# bot_power_supply.net
KiCad netlist of a schematic drawn in EAGLE
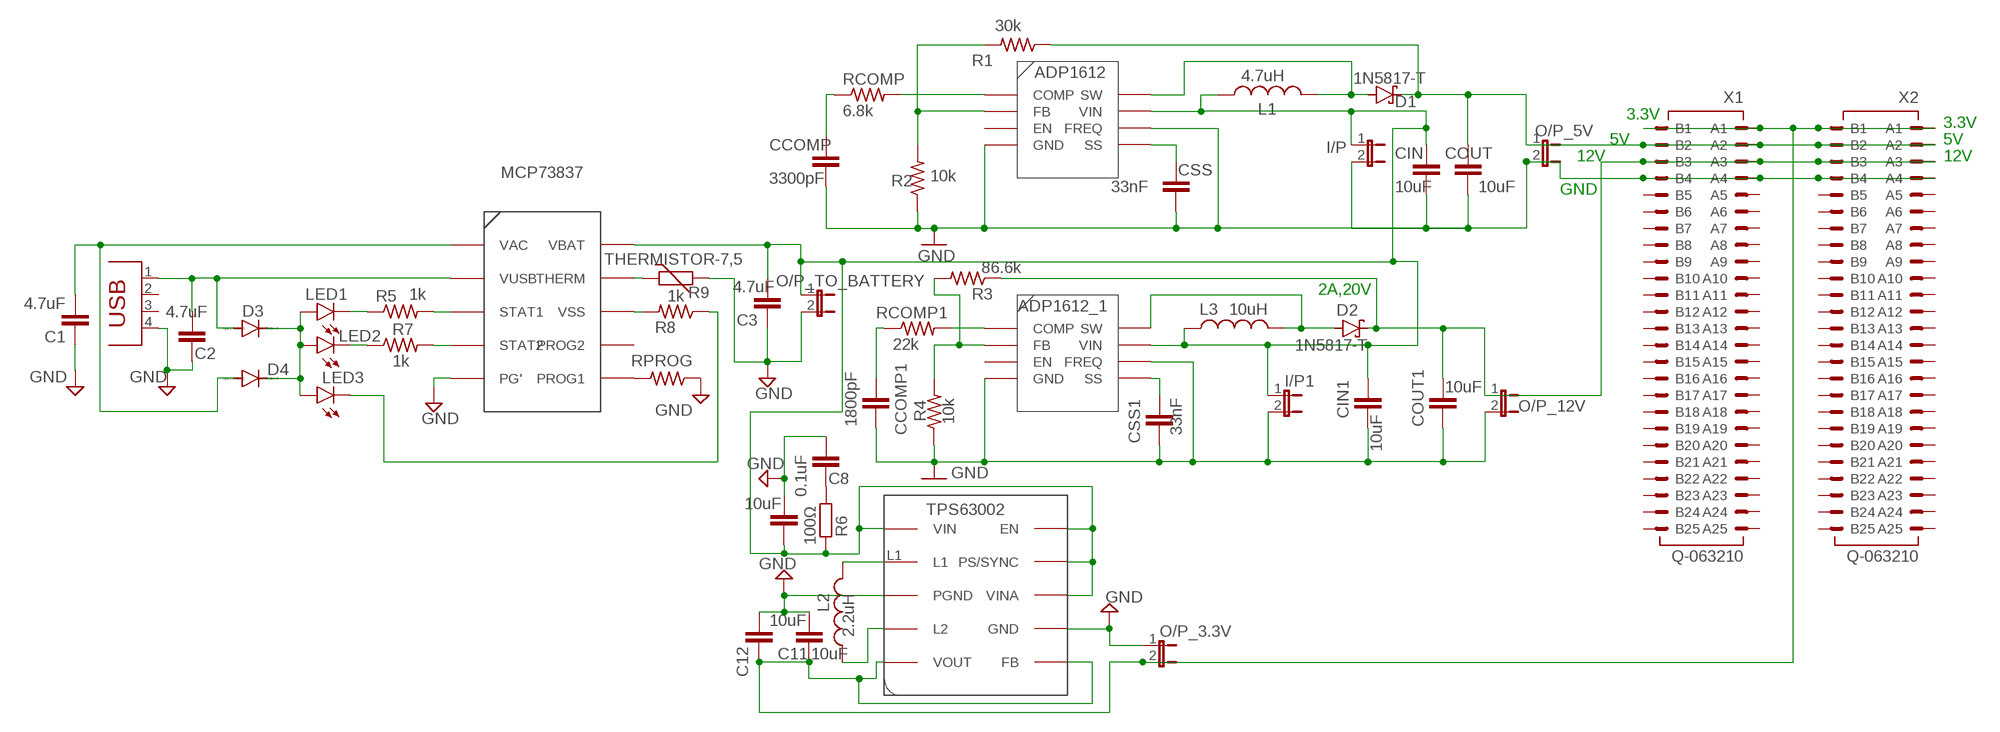
[diagram p0: schematic, sheet 1]

(export (version "E")
  (design (tool "Eeschema 10.0.6"))
  (components
    (comp (ref "ADP1612")
      (value "ADP1612_DEV")
      (footprint "eagle-import:ADP1612_FOOT")
      (libsource (lib "eagle-import") (part "ADP1612_DEV"))
    )
    (comp (ref "ADP1612_1")
      (value "ADP1612_DEV")
      (footprint "eagle-import:ADP1612_FOOT")
      (libsource (lib "eagle-import") (part "ADP1612_DEV"))
    )
    (comp (ref "C1")
      (value "4.7uF")
      (footprint "eagle-import:C2.5-3")
      (libsource (lib "eagle-import") (part "C2,5-3"))
    )
    (comp (ref "C2")
      (value "4.7uF")
      (footprint "eagle-import:C2.5-3")
      (libsource (lib "eagle-import") (part "C2,5-3"))
    )
    (comp (ref "C3")
      (value "4.7uF")
      (footprint "eagle-import:C2.5-3")
      (libsource (lib "eagle-import") (part "C2,5-3"))
    )
    (comp (ref "C8")
      (value "0.1uF")
      (footprint "eagle-import:C2.5-2")
      (libsource (lib "eagle-import") (part "C2.5/2"))
    )
    (comp (ref "C10")
      (value "10uF")
      (footprint "eagle-import:C2.5-2")
      (libsource (lib "eagle-import") (part "C2.5/2"))
    )
    (comp (ref "C11")
      (value "10uF")
      (footprint "eagle-import:C2.5-2")
      (libsource (lib "eagle-import") (part "C2.5/2"))
    )
    (comp (ref "C12")
      (value "10uF")
      (footprint "eagle-import:C2.5-2")
      (libsource (lib "eagle-import") (part "C2.5/2"))
    )
    (comp (ref "CCOMP")
      (value "3300pF")
      (footprint "eagle-import:C2.5-3")
      (libsource (lib "eagle-import") (part "C2,5-3"))
    )
    (comp (ref "CCOMP1")
      (value "1800pF")
      (footprint "eagle-import:C2.5-3")
      (libsource (lib "eagle-import") (part "C2,5-3"))
    )
    (comp (ref "CIN")
      (value "10uF")
      (footprint "eagle-import:C2.5-3")
      (libsource (lib "eagle-import") (part "C2,5-3"))
    )
    (comp (ref "CIN1")
      (value "10uF")
      (footprint "eagle-import:C2.5-3")
      (libsource (lib "eagle-import") (part "C2,5-3"))
    )
    (comp (ref "COUT")
      (value "10uF")
      (footprint "eagle-import:C2.5-3")
      (libsource (lib "eagle-import") (part "C2,5-3"))
    )
    (comp (ref "COUT1")
      (value "10uF")
      (footprint "eagle-import:C2.5-3")
      (libsource (lib "eagle-import") (part "C2,5-3"))
    )
    (comp (ref "CSS")
      (value "33nF")
      (footprint "eagle-import:C2.5-3")
      (libsource (lib "eagle-import") (part "C2,5-3"))
    )
    (comp (ref "CSS1")
      (value "33nF")
      (footprint "eagle-import:C2.5-3")
      (libsource (lib "eagle-import") (part "C2,5-3"))
    )
    (comp (ref "D1")
      (value "1N5817-T")
      (footprint "eagle-import:DO41-7.6")
      (libsource (lib "eagle-import") (part "1N5817-T"))
    )
    (comp (ref "D2")
      (value "1N5817-T")
      (footprint "eagle-import:DO41-7.6")
      (libsource (lib "eagle-import") (part "1N5817-T"))
    )
    (comp (ref "D3")
      (value "1N4004")
      (footprint "eagle-import:DO41-10")
      (libsource (lib "eagle-import") (part "1N4004"))
    )
    (comp (ref "D4")
      (value "1N4004")
      (footprint "eagle-import:DO41-10")
      (libsource (lib "eagle-import") (part "1N4004"))
    )
    (comp (ref "I/P")
      (value "JP1E")
      (footprint "eagle-import:JP1")
      (libsource (lib "eagle-import") (part "JP1E"))
    )
    (comp (ref "I/P1")
      (value "JP1E")
      (footprint "eagle-import:JP1")
      (libsource (lib "eagle-import") (part "JP1E"))
    )
    (comp (ref "L1")
      (value "4.7uH")
      (footprint "eagle-import:0204_7")
      (libsource (lib "eagle-import") (part "L-US0204/7"))
    )
    (comp (ref "L2")
      (value "2.2uH")
      (footprint "eagle-import:0207_7")
      (libsource (lib "eagle-import") (part "L-US0207/7"))
    )
    (comp (ref "L3")
      (value "10uH")
      (footprint "eagle-import:0204_7")
      (libsource (lib "eagle-import") (part "L-US0204/7"))
    )
    (comp (ref "LED1")
      (value "LED3MM")
      (footprint "eagle-import:LED3MM")
      (libsource (lib "eagle-import") (part "LED3MM"))
    )
    (comp (ref "LED2")
      (value "LEDLD260")
      (footprint "eagle-import:LD260")
      (libsource (lib "eagle-import") (part "LEDLD260"))
    )
    (comp (ref "LED3")
      (value "LED3MM")
      (footprint "eagle-import:LED3MM")
      (libsource (lib "eagle-import") (part "LED3MM"))
    )
    (comp (ref "MCP73837")
      (value "MCP73837-DEV")
      (footprint "eagle-import:MCP73837")
      (libsource (lib "eagle-import") (part "MCP73837-DEV"))
    )
    (comp (ref "O/P_3.3V")
      (value "JP1E")
      (footprint "eagle-import:JP1")
      (libsource (lib "eagle-import") (part "JP1E"))
    )
    (comp (ref "O/P_5V")
      (value "JP1E")
      (footprint "eagle-import:JP1")
      (libsource (lib "eagle-import") (part "JP1E"))
    )
    (comp (ref "O/P_12V")
      (value "JP1E")
      (footprint "eagle-import:JP1")
      (libsource (lib "eagle-import") (part "JP1E"))
    )
    (comp (ref "O/P_TO_BATTERY")
      (value "JP1E")
      (footprint "eagle-import:JP1")
      (libsource (lib "eagle-import") (part "JP1E"))
    )
    (comp (ref "R1")
      (value "30k")
      (footprint "eagle-import:0204V")
      (libsource (lib "eagle-import") (part "R-US_0204/2V"))
    )
    (comp (ref "R2")
      (value "10k")
      (footprint "eagle-import:0204V")
      (libsource (lib "eagle-import") (part "R-US_0204/2V"))
    )
    (comp (ref "R3")
      (value "86.6k")
      (footprint "eagle-import:0204V")
      (libsource (lib "eagle-import") (part "R-US_0204/2V"))
    )
    (comp (ref "R4")
      (value "10k")
      (footprint "eagle-import:0204V")
      (libsource (lib "eagle-import") (part "R-US_0204/2V"))
    )
    (comp (ref "R5")
      (value "1k")
      (footprint "eagle-import:0204V")
      (libsource (lib "eagle-import") (part "R-US_0204/2V"))
    )
    (comp (ref "R6")
      (value "100Ω")
      (footprint "eagle-import:0207_10")
      (libsource (lib "eagle-import") (part "R-EU_0207/10"))
    )
    (comp (ref "R7")
      (value "1k")
      (footprint "eagle-import:0204V")
      (libsource (lib "eagle-import") (part "R-US_0204/2V"))
    )
    (comp (ref "R8")
      (value "1k")
      (footprint "eagle-import:0204V")
      (libsource (lib "eagle-import") (part "R-US_0204/2V"))
    )
    (comp (ref "R9")
      (value "THERMISTOR-7,5")
      (footprint "eagle-import:R-7,5")
      (libsource (lib "eagle-import") (part "THERMISTOR-7,5"))
    )
    (comp (ref "RCOMP")
      (value "6.8k")
      (footprint "eagle-import:0204V")
      (libsource (lib "eagle-import") (part "R-US_0204/2V"))
    )
    (comp (ref "RCOMP1")
      (value "22k")
      (footprint "eagle-import:0204V")
      (libsource (lib "eagle-import") (part "R-US_0204/2V"))
    )
    (comp (ref "RPROG")
      (value "R-US_0204/2V")
      (footprint "eagle-import:0204V")
      (libsource (lib "eagle-import") (part "R-US_0204/2V"))
    )
    (comp (ref "TPS63002")
      (value "TPS63002")
      (footprint "eagle-import:TPS63002")
      (libsource (lib "eagle-import") (part "TPS63002"))
    )
    (comp (ref "USB")
      (value "PN61729")
      (footprint "eagle-import:PN61729")
      (libsource (lib "eagle-import") (part "PN61729"))
    )
    (comp (ref "X1")
      (value "Q-063210")
      (footprint "eagle-import:063210")
      (libsource (lib "eagle-import") (part "Q-063210"))
    )
    (comp (ref "X2")
      (value "Q-063210")
      (footprint "eagle-import:063210")
      (libsource (lib "eagle-import") (part "Q-063210"))
    )
  )
  (nets
    (net (code "1") (name "GND") (class "Default")
      (node (ref "ADP1612") (pin "FREQ") (pinfunction "FREQ_FREQ") (pintype "bidirectional"))
      (node (ref "ADP1612") (pin "GND") (pinfunction "GND_GND") (pintype "bidirectional"))
      (node (ref "ADP1612_1") (pin "FREQ") (pinfunction "FREQ_FREQ") (pintype "bidirectional"))
      (node (ref "ADP1612_1") (pin "GND") (pinfunction "GND_GND") (pintype "bidirectional"))
      (node (ref "C1") (pin "1") (pinfunction "1_1") (pintype "passive"))
      (node (ref "C10") (pin "2") (pinfunction "2_2") (pintype "passive"))
      (node (ref "C11") (pin "2") (pinfunction "2_2") (pintype "passive"))
      (node (ref "C12") (pin "2") (pinfunction "2_2") (pintype "passive"))
      (node (ref "C2") (pin "1") (pinfunction "1_1") (pintype "passive"))
      (node (ref "C3") (pin "1") (pinfunction "1_1") (pintype "passive"))
      (node (ref "C8") (pin "2") (pinfunction "2_2") (pintype "passive"))
      (node (ref "CCOMP") (pin "2") (pinfunction "2_2") (pintype "passive"))
      (node (ref "CCOMP1") (pin "2") (pinfunction "2_2") (pintype "passive"))
      (node (ref "CIN") (pin "2") (pinfunction "2_2") (pintype "passive"))
      (node (ref "CIN1") (pin "2") (pinfunction "2_2") (pintype "passive"))
      (node (ref "COUT") (pin "2") (pinfunction "2_2") (pintype "passive"))
      (node (ref "COUT1") (pin "2") (pinfunction "2_2") (pintype "passive"))
      (node (ref "CSS") (pin "2") (pinfunction "2_2") (pintype "passive"))
      (node (ref "CSS1") (pin "2") (pinfunction "2_2") (pintype "passive"))
      (node (ref "I/P") (pin "2") (pinfunction "2_2") (pintype "passive"))
      (node (ref "I/P1") (pin "2") (pinfunction "2_2") (pintype "passive"))
      (node (ref "MCP73837") (pin "PG'") (pinfunction "PG'_PG'") (pintype "bidirectional"))
      (node (ref "O/P_12V") (pin "2") (pinfunction "2_2") (pintype "passive"))
      (node (ref "O/P_3.3V") (pin "1") (pinfunction "1_1") (pintype "passive"))
      (node (ref "O/P_5V") (pin "2") (pinfunction "2_2") (pintype "passive"))
      (node (ref "O/P_TO_BATTERY") (pin "2") (pinfunction "2_2") (pintype "passive"))
      (node (ref "R2") (pin "1") (pinfunction "1_1") (pintype "passive"))
      (node (ref "R4") (pin "1") (pinfunction "1_1") (pintype "passive"))
      (node (ref "R9") (pin "2") (pinfunction "2_2") (pintype "passive"))
      (node (ref "RPROG") (pin "1") (pinfunction "1_1") (pintype "passive"))
      (node (ref "TPS63002") (pin "GND") (pinfunction "GND_GND") (pintype "bidirectional"))
      (node (ref "TPS63002") (pin "PGND") (pinfunction "PGND_PGND") (pintype "bidirectional"))
      (node (ref "USB") (pin "4") (pinfunction "4_4") (pintype "passive"))
      (node (ref "X1") (pin "A4") (pinfunction "A4_A4") (pintype "passive"))
      (node (ref "X1") (pin "B4") (pinfunction "B4_B4") (pintype "passive"))
      (node (ref "X2") (pin "A4") (pinfunction "A4_A4") (pintype "passive"))
      (node (ref "X2") (pin "B4") (pinfunction "B4_B4") (pintype "passive"))
    )
    (net (code "2") (name "Net-(ADP1612-PadCOMP)") (class "Default")
      (node (ref "ADP1612") (pin "COMP") (pinfunction "COMP_COMP") (pintype "bidirectional"))
      (node (ref "RCOMP") (pin "2") (pinfunction "2_2") (pintype "passive"))
    )
    (net (code "3") (name "Net-(ADP1612-PadFB)") (class "Default")
      (node (ref "ADP1612") (pin "FB") (pinfunction "FB_FB") (pintype "bidirectional"))
      (node (ref "R1") (pin "2") (pinfunction "2_2") (pintype "passive"))
      (node (ref "R2") (pin "2") (pinfunction "2_2") (pintype "passive"))
    )
    (net (code "4") (name "Net-(ADP1612-PadSS)") (class "Default")
      (node (ref "ADP1612") (pin "SS") (pinfunction "SS_SS") (pintype "bidirectional"))
      (node (ref "CSS") (pin "1") (pinfunction "1_1") (pintype "passive"))
    )
    (net (code "5") (name "Net-(ADP1612-PadSW)") (class "Default")
      (node (ref "ADP1612") (pin "SW") (pinfunction "SW_SW") (pintype "bidirectional"))
      (node (ref "D1") (pin "A") (pinfunction "A_A") (pintype "passive"))
      (node (ref "L1") (pin "2") (pinfunction "2_2") (pintype "passive"))
    )
    (net (code "6") (name "Net-(ADP1612-PadVIN)") (class "Default")
      (node (ref "ADP1612") (pin "VIN") (pinfunction "VIN_VIN") (pintype "bidirectional"))
      (node (ref "ADP1612_1") (pin "VIN") (pinfunction "VIN_VIN") (pintype "bidirectional"))
      (node (ref "C10") (pin "1") (pinfunction "1_1") (pintype "passive"))
      (node (ref "C3") (pin "2") (pinfunction "2_2") (pintype "passive"))
      (node (ref "CIN") (pin "1") (pinfunction "1_1") (pintype "passive"))
      (node (ref "CIN1") (pin "1") (pinfunction "1_1") (pintype "passive"))
      (node (ref "I/P") (pin "1") (pinfunction "1_1") (pintype "passive"))
      (node (ref "I/P1") (pin "1") (pinfunction "1_1") (pintype "passive"))
      (node (ref "L1") (pin "1") (pinfunction "1_1") (pintype "passive"))
      (node (ref "L3") (pin "1") (pinfunction "1_1") (pintype "passive"))
      (node (ref "MCP73837") (pin "VBAT") (pinfunction "VBAT_VBAT") (pintype "bidirectional"))
      (node (ref "O/P_TO_BATTERY") (pin "1") (pinfunction "1_1") (pintype "passive"))
      (node (ref "R6") (pin "1") (pinfunction "1_1") (pintype "passive"))
      (node (ref "TPS63002") (pin "EN") (pinfunction "EN_EN") (pintype "bidirectional"))
      (node (ref "TPS63002") (pin "PS/SYNC") (pinfunction "PS/SYNC_PS/SYNC") (pintype "bidirectional"))
      (node (ref "TPS63002") (pin "VIN") (pinfunction "VIN_VIN") (pintype "bidirectional"))
      (node (ref "TPS63002") (pin "VINA") (pinfunction "VINA_VINA") (pintype "bidirectional"))
    )
    (net (code "7") (name "Net-(ADP1612_1-PadCOMP)") (class "Default")
      (node (ref "ADP1612_1") (pin "COMP") (pinfunction "COMP_COMP") (pintype "bidirectional"))
      (node (ref "RCOMP1") (pin "2") (pinfunction "2_2") (pintype "passive"))
    )
    (net (code "8") (name "Net-(ADP1612_1-PadFB)") (class "Default")
      (node (ref "ADP1612_1") (pin "FB") (pinfunction "FB_FB") (pintype "bidirectional"))
      (node (ref "R3") (pin "2") (pinfunction "2_2") (pintype "passive"))
      (node (ref "R4") (pin "2") (pinfunction "2_2") (pintype "passive"))
    )
    (net (code "9") (name "Net-(ADP1612_1-PadSS)") (class "Default")
      (node (ref "ADP1612_1") (pin "SS") (pinfunction "SS_SS") (pintype "bidirectional"))
      (node (ref "CSS1") (pin "1") (pinfunction "1_1") (pintype "passive"))
    )
    (net (code "10") (name "Net-(ADP1612_1-PadSW)") (class "Default")
      (node (ref "ADP1612_1") (pin "SW") (pinfunction "SW_SW") (pintype "bidirectional"))
      (node (ref "D2") (pin "A") (pinfunction "A_A") (pintype "passive"))
      (node (ref "L3") (pin "2") (pinfunction "2_2") (pintype "passive"))
    )
    (net (code "11") (name "Net-(C1-Pad2)") (class "Default")
      (node (ref "C1") (pin "2") (pinfunction "2_2") (pintype "passive"))
      (node (ref "D4") (pin "A") (pinfunction "A_A") (pintype "passive"))
      (node (ref "MCP73837") (pin "VAC") (pinfunction "VAC_VAC") (pintype "bidirectional"))
    )
    (net (code "12") (name "Net-(C2-Pad2)") (class "Default")
      (node (ref "C2") (pin "2") (pinfunction "2_2") (pintype "passive"))
      (node (ref "D3") (pin "A") (pinfunction "A_A") (pintype "passive"))
      (node (ref "MCP73837") (pin "VUSB") (pinfunction "VUSB_VUSB") (pintype "bidirectional"))
      (node (ref "USB") (pin "1") (pinfunction "1_1") (pintype "passive"))
    )
    (net (code "13") (name "Net-(C8-Pad1)") (class "Default")
      (node (ref "C8") (pin "1") (pinfunction "1_1") (pintype "passive"))
      (node (ref "R6") (pin "2") (pinfunction "2_2") (pintype "passive"))
    )
    (net (code "14") (name "Net-(C11-Pad1)") (class "Default")
      (node (ref "C11") (pin "1") (pinfunction "1_1") (pintype "passive"))
      (node (ref "C12") (pin "1") (pinfunction "1_1") (pintype "passive"))
      (node (ref "O/P_3.3V") (pin "2") (pinfunction "2_2") (pintype "passive"))
      (node (ref "TPS63002") (pin "FB") (pinfunction "FB_FB") (pintype "bidirectional"))
      (node (ref "TPS63002") (pin "VOUT") (pinfunction "VOUT_VOUT") (pintype "bidirectional"))
      (node (ref "X1") (pin "A1") (pinfunction "A1_A1") (pintype "passive"))
      (node (ref "X1") (pin "B1") (pinfunction "B1_B1") (pintype "passive"))
      (node (ref "X2") (pin "A1") (pinfunction "A1_A1") (pintype "passive"))
      (node (ref "X2") (pin "B1") (pinfunction "B1_B1") (pintype "passive"))
    )
    (net (code "15") (name "Net-(CCOMP-Pad1)") (class "Default")
      (node (ref "CCOMP") (pin "1") (pinfunction "1_1") (pintype "passive"))
      (node (ref "RCOMP") (pin "1") (pinfunction "1_1") (pintype "passive"))
    )
    (net (code "16") (name "Net-(CCOMP1-Pad1)") (class "Default")
      (node (ref "CCOMP1") (pin "1") (pinfunction "1_1") (pintype "passive"))
      (node (ref "RCOMP1") (pin "1") (pinfunction "1_1") (pintype "passive"))
    )
    (net (code "17") (name "Net-(COUT-Pad1)") (class "Default")
      (node (ref "COUT") (pin "1") (pinfunction "1_1") (pintype "passive"))
      (node (ref "D1") (pin "C") (pinfunction "C_C") (pintype "passive"))
      (node (ref "O/P_5V") (pin "1") (pinfunction "1_1") (pintype "passive"))
      (node (ref "R1") (pin "1") (pinfunction "1_1") (pintype "passive"))
      (node (ref "X1") (pin "A2") (pinfunction "A2_A2") (pintype "passive"))
      (node (ref "X1") (pin "B2") (pinfunction "B2_B2") (pintype "passive"))
      (node (ref "X2") (pin "A2") (pinfunction "A2_A2") (pintype "passive"))
      (node (ref "X2") (pin "B2") (pinfunction "B2_B2") (pintype "passive"))
    )
    (net (code "18") (name "Net-(COUT1-Pad1)") (class "Default")
      (node (ref "COUT1") (pin "1") (pinfunction "1_1") (pintype "passive"))
      (node (ref "D2") (pin "C") (pinfunction "C_C") (pintype "passive"))
      (node (ref "O/P_12V") (pin "1") (pinfunction "1_1") (pintype "passive"))
      (node (ref "R3") (pin "1") (pinfunction "1_1") (pintype "passive"))
      (node (ref "X1") (pin "A3") (pinfunction "A3_A3") (pintype "passive"))
      (node (ref "X1") (pin "B3") (pinfunction "B3_B3") (pintype "passive"))
      (node (ref "X2") (pin "A3") (pinfunction "A3_A3") (pintype "passive"))
      (node (ref "X2") (pin "B3") (pinfunction "B3_B3") (pintype "passive"))
    )
    (net (code "19") (name "Net-(D3-PadC)") (class "Default")
      (node (ref "D3") (pin "C") (pinfunction "C_C") (pintype "passive"))
      (node (ref "D4") (pin "C") (pinfunction "C_C") (pintype "passive"))
      (node (ref "LED1") (pin "A") (pinfunction "A_A") (pintype "passive"))
      (node (ref "LED2") (pin "A") (pinfunction "A_A") (pintype "passive"))
      (node (ref "LED3") (pin "A") (pinfunction "A_A") (pintype "passive"))
    )
    (net (code "20") (name "Net-(L2-Pad1)") (class "Default")
      (node (ref "L2") (pin "1") (pinfunction "1_1") (pintype "passive"))
      (node (ref "TPS63002") (pin "L1") (pinfunction "L1_L1") (pintype "bidirectional"))
    )
    (net (code "21") (name "Net-(L2-Pad2)") (class "Default")
      (node (ref "L2") (pin "2") (pinfunction "2_2") (pintype "passive"))
      (node (ref "TPS63002") (pin "L2") (pinfunction "L2_L2") (pintype "bidirectional"))
    )
    (net (code "22") (name "Net-(LED1-C)") (class "Default")
      (node (ref "LED1") (pin "K") (pinfunction "C_K") (pintype "passive"))
      (node (ref "R5") (pin "1") (pinfunction "1_1") (pintype "passive"))
    )
    (net (code "23") (name "Net-(LED2-C)") (class "Default")
      (node (ref "LED2") (pin "K") (pinfunction "C_K") (pintype "passive"))
      (node (ref "R7") (pin "1") (pinfunction "1_1") (pintype "passive"))
    )
    (net (code "24") (name "Net-(LED3-C)") (class "Default")
      (node (ref "LED3") (pin "K") (pinfunction "C_K") (pintype "passive"))
      (node (ref "R8") (pin "1") (pinfunction "1_1") (pintype "passive"))
    )
    (net (code "25") (name "Net-(MCP73837-PadPROG1)") (class "Default")
      (node (ref "MCP73837") (pin "PROG1") (pinfunction "PROG1_PROG1") (pintype "bidirectional"))
      (node (ref "RPROG") (pin "2") (pinfunction "2_2") (pintype "passive"))
    )
    (net (code "26") (name "Net-(MCP73837-PadSTAT1)") (class "Default")
      (node (ref "MCP73837") (pin "STAT1") (pinfunction "STAT1_STAT1") (pintype "bidirectional"))
      (node (ref "R5") (pin "2") (pinfunction "2_2") (pintype "passive"))
    )
    (net (code "27") (name "Net-(MCP73837-PadSTAT2)") (class "Default")
      (node (ref "MCP73837") (pin "STAT2") (pinfunction "STAT2_STAT2") (pintype "bidirectional"))
      (node (ref "R7") (pin "2") (pinfunction "2_2") (pintype "passive"))
    )
    (net (code "28") (name "Net-(MCP73837-PadTHERM)") (class "Default")
      (node (ref "MCP73837") (pin "THERM") (pinfunction "THERM_THERM") (pintype "bidirectional"))
      (node (ref "R9") (pin "1") (pinfunction "1_1") (pintype "passive"))
    )
    (net (code "29") (name "Net-(MCP73837-PadVSS)") (class "Default")
      (node (ref "MCP73837") (pin "VSS") (pinfunction "VSS_VSS") (pintype "bidirectional"))
      (node (ref "R8") (pin "2") (pinfunction "2_2") (pintype "passive"))
    )
    (net (code "30") (name "unconnected-(ADP1612-PadEN)") (class "Default")
      (node (ref "ADP1612") (pin "EN") (pinfunction "EN_EN") (pintype "bidirectional"))
    )
    (net (code "31") (name "unconnected-(ADP1612_1-PadEN)") (class "Default")
      (node (ref "ADP1612_1") (pin "EN") (pinfunction "EN_EN") (pintype "bidirectional"))
    )
    (net (code "32") (name "unconnected-(MCP73837-PadPROG2)") (class "Default")
      (node (ref "MCP73837") (pin "PROG2") (pinfunction "PROG2_PROG2") (pintype "bidirectional"))
    )
    (net (code "33") (name "unconnected-(USB-Pad2)") (class "Default")
      (node (ref "USB") (pin "2") (pinfunction "2_2") (pintype "passive"))
    )
    (net (code "34") (name "unconnected-(USB-Pad3)") (class "Default")
      (node (ref "USB") (pin "3") (pinfunction "3_3") (pintype "passive"))
    )
    (net (code "35") (name "unconnected-(X1-PadA5)") (class "Default")
      (node (ref "X1") (pin "A5") (pinfunction "A5_A5") (pintype "passive"))
    )
    (net (code "36") (name "unconnected-(X1-PadA6)") (class "Default")
      (node (ref "X1") (pin "A6") (pinfunction "A6_A6") (pintype "passive"))
    )
    (net (code "37") (name "unconnected-(X1-PadA7)") (class "Default")
      (node (ref "X1") (pin "A7") (pinfunction "A7_A7") (pintype "passive"))
    )
    (net (code "38") (name "unconnected-(X1-PadA8)") (class "Default")
      (node (ref "X1") (pin "A8") (pinfunction "A8_A8") (pintype "passive"))
    )
    (net (code "39") (name "unconnected-(X1-PadA9)") (class "Default")
      (node (ref "X1") (pin "A9") (pinfunction "A9_A9") (pintype "passive"))
    )
    (net (code "40") (name "unconnected-(X1-PadA10)") (class "Default")
      (node (ref "X1") (pin "A10") (pinfunction "A10_A10") (pintype "passive"))
    )
    (net (code "41") (name "unconnected-(X1-PadA11)") (class "Default")
      (node (ref "X1") (pin "A11") (pinfunction "A11_A11") (pintype "passive"))
    )
    (net (code "42") (name "unconnected-(X1-PadA12)") (class "Default")
      (node (ref "X1") (pin "A12") (pinfunction "A12_A12") (pintype "passive"))
    )
    (net (code "43") (name "unconnected-(X1-PadA13)") (class "Default")
      (node (ref "X1") (pin "A13") (pinfunction "A13_A13") (pintype "passive"))
    )
    (net (code "44") (name "unconnected-(X1-PadA14)") (class "Default")
      (node (ref "X1") (pin "A14") (pinfunction "A14_A14") (pintype "passive"))
    )
    (net (code "45") (name "unconnected-(X1-PadA15)") (class "Default")
      (node (ref "X1") (pin "A15") (pinfunction "A15_A15") (pintype "passive"))
    )
    (net (code "46") (name "unconnected-(X1-PadA16)") (class "Default")
      (node (ref "X1") (pin "A16") (pinfunction "A16_A16") (pintype "passive"))
    )
    (net (code "47") (name "unconnected-(X1-PadA17)") (class "Default")
      (node (ref "X1") (pin "A17") (pinfunction "A17_A17") (pintype "passive"))
    )
    (net (code "48") (name "unconnected-(X1-PadA18)") (class "Default")
      (node (ref "X1") (pin "A18") (pinfunction "A18_A18") (pintype "passive"))
    )
    (net (code "49") (name "unconnected-(X1-PadA19)") (class "Default")
      (node (ref "X1") (pin "A19") (pinfunction "A19_A19") (pintype "passive"))
    )
    (net (code "50") (name "unconnected-(X1-PadA20)") (class "Default")
      (node (ref "X1") (pin "A20") (pinfunction "A20_A20") (pintype "passive"))
    )
    (net (code "51") (name "unconnected-(X1-PadA21)") (class "Default")
      (node (ref "X1") (pin "A21") (pinfunction "A21_A21") (pintype "passive"))
    )
    (net (code "52") (name "unconnected-(X1-PadA22)") (class "Default")
      (node (ref "X1") (pin "A22") (pinfunction "A22_A22") (pintype "passive"))
    )
    (net (code "53") (name "unconnected-(X1-PadA23)") (class "Default")
      (node (ref "X1") (pin "A23") (pinfunction "A23_A23") (pintype "passive"))
    )
    (net (code "54") (name "unconnected-(X1-PadA24)") (class "Default")
      (node (ref "X1") (pin "A24") (pinfunction "A24_A24") (pintype "passive"))
    )
    (net (code "55") (name "unconnected-(X1-PadA25)") (class "Default")
      (node (ref "X1") (pin "A25") (pinfunction "A25_A25") (pintype "passive"))
    )
    (net (code "56") (name "unconnected-(X1-PadB5)") (class "Default")
      (node (ref "X1") (pin "B5") (pinfunction "B5_B5") (pintype "passive"))
    )
    (net (code "57") (name "unconnected-(X1-PadB6)") (class "Default")
      (node (ref "X1") (pin "B6") (pinfunction "B6_B6") (pintype "passive"))
    )
    (net (code "58") (name "unconnected-(X1-PadB7)") (class "Default")
      (node (ref "X1") (pin "B7") (pinfunction "B7_B7") (pintype "passive"))
    )
    (net (code "59") (name "unconnected-(X1-PadB8)") (class "Default")
      (node (ref "X1") (pin "B8") (pinfunction "B8_B8") (pintype "passive"))
    )
    (net (code "60") (name "unconnected-(X1-PadB9)") (class "Default")
      (node (ref "X1") (pin "B9") (pinfunction "B9_B9") (pintype "passive"))
    )
    (net (code "61") (name "unconnected-(X1-PadB10)") (class "Default")
      (node (ref "X1") (pin "B10") (pinfunction "B10_B10") (pintype "passive"))
    )
    (net (code "62") (name "unconnected-(X1-PadB11)") (class "Default")
      (node (ref "X1") (pin "B11") (pinfunction "B11_B11") (pintype "passive"))
    )
    (net (code "63") (name "unconnected-(X1-PadB12)") (class "Default")
      (node (ref "X1") (pin "B12") (pinfunction "B12_B12") (pintype "passive"))
    )
    (net (code "64") (name "unconnected-(X1-PadB13)") (class "Default")
      (node (ref "X1") (pin "B13") (pinfunction "B13_B13") (pintype "passive"))
    )
    (net (code "65") (name "unconnected-(X1-PadB14)") (class "Default")
      (node (ref "X1") (pin "B14") (pinfunction "B14_B14") (pintype "passive"))
    )
    (net (code "66") (name "unconnected-(X1-PadB15)") (class "Default")
      (node (ref "X1") (pin "B15") (pinfunction "B15_B15") (pintype "passive"))
    )
    (net (code "67") (name "unconnected-(X1-PadB16)") (class "Default")
      (node (ref "X1") (pin "B16") (pinfunction "B16_B16") (pintype "passive"))
    )
    (net (code "68") (name "unconnected-(X1-PadB17)") (class "Default")
      (node (ref "X1") (pin "B17") (pinfunction "B17_B17") (pintype "passive"))
    )
    (net (code "69") (name "unconnected-(X1-PadB18)") (class "Default")
      (node (ref "X1") (pin "B18") (pinfunction "B18_B18") (pintype "passive"))
    )
    (net (code "70") (name "unconnected-(X1-PadB19)") (class "Default")
      (node (ref "X1") (pin "B19") (pinfunction "B19_B19") (pintype "passive"))
    )
    (net (code "71") (name "unconnected-(X1-PadB20)") (class "Default")
      (node (ref "X1") (pin "B20") (pinfunction "B20_B20") (pintype "passive"))
    )
    (net (code "72") (name "unconnected-(X1-PadB21)") (class "Default")
      (node (ref "X1") (pin "B21") (pinfunction "B21_B21") (pintype "passive"))
    )
    (net (code "73") (name "unconnected-(X1-PadB22)") (class "Default")
      (node (ref "X1") (pin "B22") (pinfunction "B22_B22") (pintype "passive"))
    )
    (net (code "74") (name "unconnected-(X1-PadB23)") (class "Default")
      (node (ref "X1") (pin "B23") (pinfunction "B23_B23") (pintype "passive"))
    )
    (net (code "75") (name "unconnected-(X1-PadB24)") (class "Default")
      (node (ref "X1") (pin "B24") (pinfunction "B24_B24") (pintype "passive"))
    )
    (net (code "76") (name "unconnected-(X1-PadB25)") (class "Default")
      (node (ref "X1") (pin "B25") (pinfunction "B25_B25") (pintype "passive"))
    )
    (net (code "77") (name "unconnected-(X2-PadA5)") (class "Default")
      (node (ref "X2") (pin "A5") (pinfunction "A5_A5") (pintype "passive"))
    )
    (net (code "78") (name "unconnected-(X2-PadA6)") (class "Default")
      (node (ref "X2") (pin "A6") (pinfunction "A6_A6") (pintype "passive"))
    )
    (net (code "79") (name "unconnected-(X2-PadA7)") (class "Default")
      (node (ref "X2") (pin "A7") (pinfunction "A7_A7") (pintype "passive"))
    )
    (net (code "80") (name "unconnected-(X2-PadA8)") (class "Default")
      (node (ref "X2") (pin "A8") (pinfunction "A8_A8") (pintype "passive"))
    )
    (net (code "81") (name "unconnected-(X2-PadA9)") (class "Default")
      (node (ref "X2") (pin "A9") (pinfunction "A9_A9") (pintype "passive"))
    )
    (net (code "82") (name "unconnected-(X2-PadA10)") (class "Default")
      (node (ref "X2") (pin "A10") (pinfunction "A10_A10") (pintype "passive"))
    )
    (net (code "83") (name "unconnected-(X2-PadA11)") (class "Default")
      (node (ref "X2") (pin "A11") (pinfunction "A11_A11") (pintype "passive"))
    )
    (net (code "84") (name "unconnected-(X2-PadA12)") (class "Default")
      (node (ref "X2") (pin "A12") (pinfunction "A12_A12") (pintype "passive"))
    )
    (net (code "85") (name "unconnected-(X2-PadA13)") (class "Default")
      (node (ref "X2") (pin "A13") (pinfunction "A13_A13") (pintype "passive"))
    )
    (net (code "86") (name "unconnected-(X2-PadA14)") (class "Default")
      (node (ref "X2") (pin "A14") (pinfunction "A14_A14") (pintype "passive"))
    )
    (net (code "87") (name "unconnected-(X2-PadA15)") (class "Default")
      (node (ref "X2") (pin "A15") (pinfunction "A15_A15") (pintype "passive"))
    )
    (net (code "88") (name "unconnected-(X2-PadA16)") (class "Default")
      (node (ref "X2") (pin "A16") (pinfunction "A16_A16") (pintype "passive"))
    )
    (net (code "89") (name "unconnected-(X2-PadA17)") (class "Default")
      (node (ref "X2") (pin "A17") (pinfunction "A17_A17") (pintype "passive"))
    )
    (net (code "90") (name "unconnected-(X2-PadA18)") (class "Default")
      (node (ref "X2") (pin "A18") (pinfunction "A18_A18") (pintype "passive"))
    )
    (net (code "91") (name "unconnected-(X2-PadA19)") (class "Default")
      (node (ref "X2") (pin "A19") (pinfunction "A19_A19") (pintype "passive"))
    )
    (net (code "92") (name "unconnected-(X2-PadA20)") (class "Default")
      (node (ref "X2") (pin "A20") (pinfunction "A20_A20") (pintype "passive"))
    )
    (net (code "93") (name "unconnected-(X2-PadA21)") (class "Default")
      (node (ref "X2") (pin "A21") (pinfunction "A21_A21") (pintype "passive"))
    )
    (net (code "94") (name "unconnected-(X2-PadA22)") (class "Default")
      (node (ref "X2") (pin "A22") (pinfunction "A22_A22") (pintype "passive"))
    )
    (net (code "95") (name "unconnected-(X2-PadA23)") (class "Default")
      (node (ref "X2") (pin "A23") (pinfunction "A23_A23") (pintype "passive"))
    )
    (net (code "96") (name "unconnected-(X2-PadA24)") (class "Default")
      (node (ref "X2") (pin "A24") (pinfunction "A24_A24") (pintype "passive"))
    )
    (net (code "97") (name "unconnected-(X2-PadA25)") (class "Default")
      (node (ref "X2") (pin "A25") (pinfunction "A25_A25") (pintype "passive"))
    )
    (net (code "98") (name "unconnected-(X2-PadB5)") (class "Default")
      (node (ref "X2") (pin "B5") (pinfunction "B5_B5") (pintype "passive"))
    )
    (net (code "99") (name "unconnected-(X2-PadB6)") (class "Default")
      (node (ref "X2") (pin "B6") (pinfunction "B6_B6") (pintype "passive"))
    )
    (net (code "100") (name "unconnected-(X2-PadB7)") (class "Default")
      (node (ref "X2") (pin "B7") (pinfunction "B7_B7") (pintype "passive"))
    )
    (net (code "101") (name "unconnected-(X2-PadB8)") (class "Default")
      (node (ref "X2") (pin "B8") (pinfunction "B8_B8") (pintype "passive"))
    )
    (net (code "102") (name "unconnected-(X2-PadB9)") (class "Default")
      (node (ref "X2") (pin "B9") (pinfunction "B9_B9") (pintype "passive"))
    )
    (net (code "103") (name "unconnected-(X2-PadB10)") (class "Default")
      (node (ref "X2") (pin "B10") (pinfunction "B10_B10") (pintype "passive"))
    )
    (net (code "104") (name "unconnected-(X2-PadB11)") (class "Default")
      (node (ref "X2") (pin "B11") (pinfunction "B11_B11") (pintype "passive"))
    )
    (net (code "105") (name "unconnected-(X2-PadB12)") (class "Default")
      (node (ref "X2") (pin "B12") (pinfunction "B12_B12") (pintype "passive"))
    )
    (net (code "106") (name "unconnected-(X2-PadB13)") (class "Default")
      (node (ref "X2") (pin "B13") (pinfunction "B13_B13") (pintype "passive"))
    )
    (net (code "107") (name "unconnected-(X2-PadB14)") (class "Default")
      (node (ref "X2") (pin "B14") (pinfunction "B14_B14") (pintype "passive"))
    )
    (net (code "108") (name "unconnected-(X2-PadB15)") (class "Default")
      (node (ref "X2") (pin "B15") (pinfunction "B15_B15") (pintype "passive"))
    )
    (net (code "109") (name "unconnected-(X2-PadB16)") (class "Default")
      (node (ref "X2") (pin "B16") (pinfunction "B16_B16") (pintype "passive"))
    )
    (net (code "110") (name "unconnected-(X2-PadB17)") (class "Default")
      (node (ref "X2") (pin "B17") (pinfunction "B17_B17") (pintype "passive"))
    )
    (net (code "111") (name "unconnected-(X2-PadB18)") (class "Default")
      (node (ref "X2") (pin "B18") (pinfunction "B18_B18") (pintype "passive"))
    )
    (net (code "112") (name "unconnected-(X2-PadB19)") (class "Default")
      (node (ref "X2") (pin "B19") (pinfunction "B19_B19") (pintype "passive"))
    )
    (net (code "113") (name "unconnected-(X2-PadB20)") (class "Default")
      (node (ref "X2") (pin "B20") (pinfunction "B20_B20") (pintype "passive"))
    )
    (net (code "114") (name "unconnected-(X2-PadB21)") (class "Default")
      (node (ref "X2") (pin "B21") (pinfunction "B21_B21") (pintype "passive"))
    )
    (net (code "115") (name "unconnected-(X2-PadB22)") (class "Default")
      (node (ref "X2") (pin "B22") (pinfunction "B22_B22") (pintype "passive"))
    )
    (net (code "116") (name "unconnected-(X2-PadB23)") (class "Default")
      (node (ref "X2") (pin "B23") (pinfunction "B23_B23") (pintype "passive"))
    )
    (net (code "117") (name "unconnected-(X2-PadB24)") (class "Default")
      (node (ref "X2") (pin "B24") (pinfunction "B24_B24") (pintype "passive"))
    )
    (net (code "118") (name "unconnected-(X2-PadB25)") (class "Default")
      (node (ref "X2") (pin "B25") (pinfunction "B25_B25") (pintype "passive"))
    )
  )
)
